# V3.net
KiCad netlist of a schematic drawn in Altium Designer
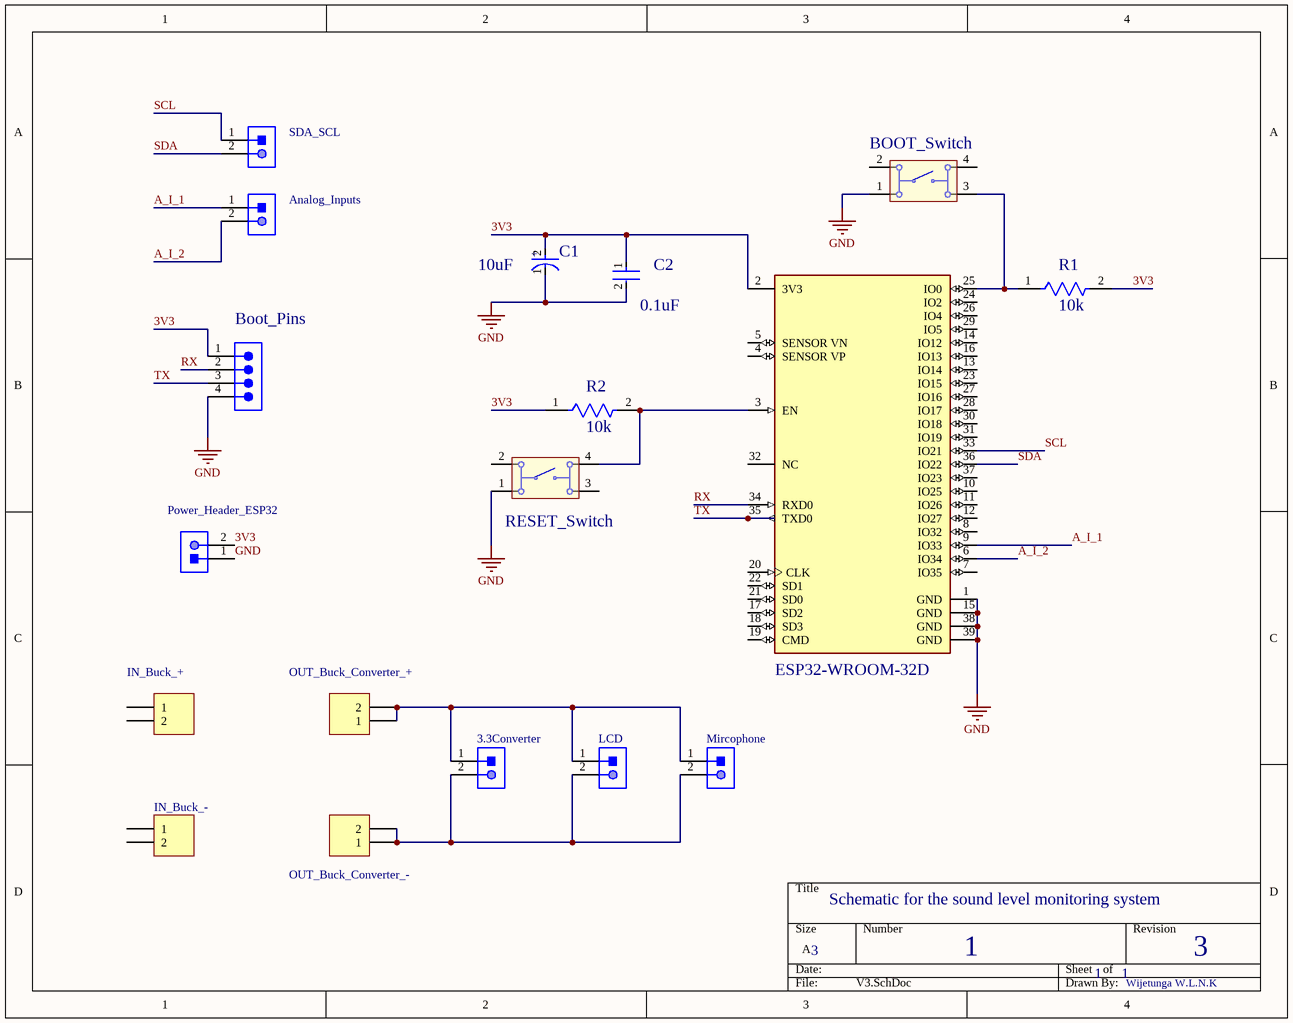
[diagram p0: V3.SchDoc]

(export (version "E")
  (design (tool "Eeschema 10.0.6"))
  (components
    (comp (ref "3.3Converter")
      (value "B2P-VH(LF)(SN)")
      (footprint "JST-B2P-VH(LF)(SN)_V")
      (fields (field (name "MANUFACTURER") "JST"))
      (libsource (lib "University of Moratuwa") (part "CN-1P-M-R2"))
    )
    (comp (ref "Analog_Inputs")
      (value "B2P-VH(LF)(SN)")
      (footprint "JST-B2P-VH(LF)(SN)_V")
      (fields (field (name "MANUFACTURER") "JST"))
      (libsource (lib "University of Moratuwa") (part "CN-1P-M-R2"))
    )
    (comp (ref "Boot_Pins")
      (value "TSW-104-08-L-S")
      (footprint "SMTC-TSW-104-08-X-S")
      (description "0.025\" SQ Post Header, Through-hole, Vertical, -55 to 125 degC, 2.54 mm Pitch, 4-Pin, Male, RoHS")
      (fields (field (name "MANUFACTURER") "Samtec"))
      (libsource (lib "Altium Content Vault") (part "SMTC-TSW-104-08-X-S"))
    )
    (comp (ref "BOOT_Switch")
      (value "430471025826")
      (footprint "430471025826")
      (description "WS-TASV SMD Tact Switch 6X6 mm")
      (fields (field (name "MANUFACTURER") "Wuerth Elektronik"))
      (libsource (lib "Altium Content Vault") (part "WE-TACT-SW-4_A"))
    )
    (comp (ref "C1")
      (value "10uF")
      (footprint "FP-RAD-TH-D_10_0_5-L_16_1-MFG")
      (description "Aluminum Electrolytic Capacitors (Radial Lead Type) AEC-Q200 Qualified 1000uF ±20% 10V")
      (fields (field (name "VOLTAGE") "10V") (field (name "TOLERANCE") "20%"))
      (libsource (lib "Altium Content Vault") (part "a00bbbee19879c290e62620ae7e47b1"))
    )
    (comp (ref "C2")
      (value "0.1uF")
      (footprint "FP-RCE0DB-MFG")
      (description "Cap Ceramic 100nF 50V X7R ±10% Radial 2.5mm +125°C Ammo Pack")
      (fields (field (name "TOLERANCE") "10%"))
      (libsource (lib "Altium Content Vault") (part "b4654b650e69147ec39a6b967a45e02"))
    )
    (comp (ref "ESP32-WROOM-32D")
      (value "ESP32-WROOM-32D")
      (footprint "FP-ESP32-WROOM-32D-MFG")
      (description "WIFI MODULE 32MBITS SPI FLASH")
      (fields
        (field (name "OCTOPART") "https://octopart.com/esp32-wroom-32d-espressif+systems-91040050")
        (field (name "MANUFACTURER") "Espressif Systems")
      )
      (libsource (lib "Altium Content Vault") (part "a031a76f8c27026a7a7f4657ff233a3"))
    )
    (comp (ref "IN_Buck_+")
      (value "Header 2")
      (footprint "HDR1X2")
      (description "Header, 2-Pin")
      (fields (field (name "PUBLISHER") "Altium Limited"))
      (libsource (lib "") (part "Header 2H_1"))
    )
    (comp (ref "IN_Buck_-")
      (value "Header 2")
      (footprint "HDR1X2")
      (description "Header, 2-Pin")
      (fields (field (name "PUBLISHER") "Altium Limited"))
      (libsource (lib "") (part "Header 2H_1"))
    )
    (comp (ref "LCD")
      (value "B2P-VH(LF)(SN)")
      (footprint "JST-B2P-VH(LF)(SN)_V")
      (fields (field (name "MANUFACTURER") "JST"))
      (libsource (lib "University of Moratuwa") (part "CN-1P-M-R2"))
    )
    (comp (ref "Mircophone")
      (value "B2P-VH(LF)(SN)")
      (footprint "JST-B2P-VH(LF)(SN)_V")
      (fields (field (name "MANUFACTURER") "JST"))
      (libsource (lib "University of Moratuwa") (part "CN-1P-M-R2"))
    )
    (comp (ref "OUT_Buck_Converter_+")
      (value "Header 2")
      (footprint "HDR1X2")
      (description "Header, 2-Pin")
      (fields (field (name "PUBLISHER") "Altium Limited"))
      (libsource (lib "University of Moratuwa") (part "Header 2H"))
    )
    (comp (ref "OUT_Buck_Converter_-")
      (value "Header 2")
      (footprint "HDR1X2")
      (description "Header, 2-Pin")
      (fields (field (name "PUBLISHER") "Altium Limited"))
      (libsource (lib "University of Moratuwa") (part "Header 2H"))
    )
    (comp (ref "Power_Header_ESP32")
      (value "B2P-VH(LF)(SN)")
      (footprint "JST-B2P-VH(LF)(SN)_V")
      (fields (field (name "MANUFACTURER") "JST"))
      (libsource (lib "") (part "CN-1P-M-R2_1"))
    )
    (comp (ref "R1")
      (value "10k")
      (footprint "FP-MBB0207-MFG")
      (description "RES 10K OHM 0.6W 1% AXIAL")
      (fields (field (name "TOLERANCE") "1%"))
      (libsource (lib "Altium Content Vault") (part "1029c3af85768c4190bb7ad29bc67b5"))
    )
    (comp (ref "R2")
      (value "10k")
      (footprint "FP-MBB0207-MFG")
      (description "RES 10K OHM 0.6W 1% AXIAL")
      (fields (field (name "TOLERANCE") "1%"))
      (libsource (lib "Altium Content Vault") (part "1029c3af85768c4190bb7ad29bc67b5"))
    )
    (comp (ref "RESET_Switch")
      (value "430471025826")
      (footprint "430471025826")
      (description "WS-TASV SMD Tact Switch 6X6 mm")
      (fields (field (name "MANUFACTURER") "Wuerth Elektronik"))
      (libsource (lib "Altium Content Vault") (part "WE-TACT-SW-4_A"))
    )
    (comp (ref "SDA_SCL")
      (value "B2P-VH(LF)(SN)")
      (footprint "JST-B2P-VH(LF)(SN)_V")
      (fields (field (name "MANUFACTURER") "JST"))
      (libsource (lib "University of Moratuwa") (part "CN-1P-M-R2"))
    )
  )
  (nets
    (net (code "1") (name "/3V3") (class "Default")
      (node (ref "Boot_Pins") (pin "1") (pinfunction "1_1") (pintype "passive"))
      (node (ref "C1") (pin "2") (pinfunction "A_2") (pintype "passive"))
      (node (ref "C2") (pin "1") (pinfunction "1_1") (pintype "passive"))
      (node (ref "ESP32-WROOM-32D") (pin "2") (pinfunction "3V3_2") (pintype "power_in"))
      (node (ref "Power_Header_ESP32") (pin "2") (pinfunction "2_2") (pintype "passive"))
      (node (ref "R1") (pin "2") (pinfunction "2_2") (pintype "passive"))
      (node (ref "R2") (pin "1") (pinfunction "1_1") (pintype "passive"))
    )
    (net (code "2") (name "/A_I_1") (class "Default")
      (node (ref "Analog_Inputs") (pin "1") (pinfunction "1_1") (pintype "passive"))
      (node (ref "ESP32-WROOM-32D") (pin "9") (pinfunction "IO33_9") (pintype "bidirectional"))
    )
    (net (code "3") (name "/A_I_2") (class "Default")
      (node (ref "Analog_Inputs") (pin "2") (pinfunction "2_2") (pintype "passive"))
      (node (ref "ESP32-WROOM-32D") (pin "6") (pinfunction "IO34_6") (pintype "bidirectional"))
    )
    (net (code "4") (name "/RX") (class "Default")
      (node (ref "Boot_Pins") (pin "2") (pinfunction "2_2") (pintype "passive"))
      (node (ref "ESP32-WROOM-32D") (pin "34") (pinfunction "RXD0_34") (pintype "input"))
    )
    (net (code "5") (name "/SCL") (class "Default")
      (node (ref "ESP32-WROOM-32D") (pin "33") (pinfunction "IO21_33") (pintype "bidirectional"))
      (node (ref "SDA_SCL") (pin "1") (pinfunction "1_1") (pintype "passive"))
    )
    (net (code "6") (name "/SDA") (class "Default")
      (node (ref "ESP32-WROOM-32D") (pin "36") (pinfunction "IO22_36") (pintype "bidirectional"))
      (node (ref "SDA_SCL") (pin "2") (pinfunction "2_2") (pintype "passive"))
    )
    (net (code "7") (name "/TX") (class "Default")
      (node (ref "Boot_Pins") (pin "3") (pinfunction "3_3") (pintype "passive"))
      (node (ref "ESP32-WROOM-32D") (pin "35") (pinfunction "TXD0_35") (pintype "output"))
    )
    (net (code "8") (name "GND") (class "Default")
      (node (ref "BOOT_Switch") (pin "1") (pinfunction "1_1") (pintype "passive"))
      (node (ref "Boot_Pins") (pin "4") (pinfunction "4_4") (pintype "passive"))
      (node (ref "C1") (pin "1") (pinfunction "C_1") (pintype "passive"))
      (node (ref "C2") (pin "2") (pinfunction "2_2") (pintype "passive"))
      (node (ref "ESP32-WROOM-32D") (pin "1") (pinfunction "GND_1") (pintype "power_in"))
      (node (ref "ESP32-WROOM-32D") (pin "15") (pinfunction "GND_15") (pintype "power_in"))
      (node (ref "ESP32-WROOM-32D") (pin "38") (pinfunction "GND_38") (pintype "power_in"))
      (node (ref "ESP32-WROOM-32D") (pin "39") (pinfunction "GND_39") (pintype "power_in"))
      (node (ref "Power_Header_ESP32") (pin "1") (pinfunction "1_1") (pintype "passive"))
      (node (ref "RESET_Switch") (pin "1") (pinfunction "1_1") (pintype "passive"))
    )
    (net (code "9") (name "Net-(3.3Converter-Pad1)") (class "Default")
      (node (ref "3.3Converter") (pin "1") (pinfunction "1_1") (pintype "passive"))
      (node (ref "LCD") (pin "1") (pinfunction "1_1") (pintype "passive"))
      (node (ref "Mircophone") (pin "1") (pinfunction "1_1") (pintype "passive"))
      (node (ref "OUT_Buck_Converter_+") (pin "1") (pinfunction "1_1") (pintype "passive"))
      (node (ref "OUT_Buck_Converter_+") (pin "2") (pinfunction "2_2") (pintype "passive"))
    )
    (net (code "10") (name "Net-(3.3Converter-Pad2)") (class "Default")
      (node (ref "3.3Converter") (pin "2") (pinfunction "2_2") (pintype "passive"))
      (node (ref "LCD") (pin "2") (pinfunction "2_2") (pintype "passive"))
      (node (ref "Mircophone") (pin "2") (pinfunction "2_2") (pintype "passive"))
      (node (ref "OUT_Buck_Converter_-") (pin "1") (pinfunction "1_1") (pintype "passive"))
      (node (ref "OUT_Buck_Converter_-") (pin "2") (pinfunction "2_2") (pintype "passive"))
    )
    (net (code "11") (name "Net-(ESP32-WROOM-32D-EN)") (class "Default")
      (node (ref "ESP32-WROOM-32D") (pin "3") (pinfunction "EN_3") (pintype "input"))
      (node (ref "R2") (pin "2") (pinfunction "2_2") (pintype "passive"))
      (node (ref "RESET_Switch") (pin "4") (pinfunction "4_4") (pintype "passive"))
    )
    (net (code "12") (name "Net-(ESP32-WROOM-32D-IO0)") (class "Default")
      (node (ref "BOOT_Switch") (pin "3") (pinfunction "3_3") (pintype "passive"))
      (node (ref "ESP32-WROOM-32D") (pin "25") (pinfunction "IO0_25") (pintype "bidirectional"))
      (node (ref "R1") (pin "1") (pinfunction "1_1") (pintype "passive"))
    )
    (net (code "13") (name "unconnected-(BOOT_Switch-Pad2)") (class "Default")
      (node (ref "BOOT_Switch") (pin "2") (pinfunction "2_2") (pintype "passive"))
    )
    (net (code "14") (name "unconnected-(BOOT_Switch-Pad4)") (class "Default")
      (node (ref "BOOT_Switch") (pin "4") (pinfunction "4_4") (pintype "passive"))
    )
    (net (code "15") (name "unconnected-(ESP32-WROOM-32D-CLK-Pad20)") (class "Default")
      (node (ref "ESP32-WROOM-32D") (pin "20") (pinfunction "CLK_20") (pintype "input"))
    )
    (net (code "16") (name "unconnected-(ESP32-WROOM-32D-CMD-Pad19)") (class "Default")
      (node (ref "ESP32-WROOM-32D") (pin "19") (pinfunction "CMD_19") (pintype "bidirectional"))
    )
    (net (code "17") (name "unconnected-(ESP32-WROOM-32D-IO2-Pad24)") (class "Default")
      (node (ref "ESP32-WROOM-32D") (pin "24") (pinfunction "IO2_24") (pintype "bidirectional"))
    )
    (net (code "18") (name "unconnected-(ESP32-WROOM-32D-IO4-Pad26)") (class "Default")
      (node (ref "ESP32-WROOM-32D") (pin "26") (pinfunction "IO4_26") (pintype "bidirectional"))
    )
    (net (code "19") (name "unconnected-(ESP32-WROOM-32D-IO5-Pad29)") (class "Default")
      (node (ref "ESP32-WROOM-32D") (pin "29") (pinfunction "IO5_29") (pintype "bidirectional"))
    )
    (net (code "20") (name "unconnected-(ESP32-WROOM-32D-IO12-Pad14)") (class "Default")
      (node (ref "ESP32-WROOM-32D") (pin "14") (pinfunction "IO12_14") (pintype "bidirectional"))
    )
    (net (code "21") (name "unconnected-(ESP32-WROOM-32D-IO13-Pad16)") (class "Default")
      (node (ref "ESP32-WROOM-32D") (pin "16") (pinfunction "IO13_16") (pintype "bidirectional"))
    )
    (net (code "22") (name "unconnected-(ESP32-WROOM-32D-IO14-Pad13)") (class "Default")
      (node (ref "ESP32-WROOM-32D") (pin "13") (pinfunction "IO14_13") (pintype "bidirectional"))
    )
    (net (code "23") (name "unconnected-(ESP32-WROOM-32D-IO15-Pad23)") (class "Default")
      (node (ref "ESP32-WROOM-32D") (pin "23") (pinfunction "IO15_23") (pintype "bidirectional"))
    )
    (net (code "24") (name "unconnected-(ESP32-WROOM-32D-IO16-Pad27)") (class "Default")
      (node (ref "ESP32-WROOM-32D") (pin "27") (pinfunction "IO16_27") (pintype "bidirectional"))
    )
    (net (code "25") (name "unconnected-(ESP32-WROOM-32D-IO17-Pad28)") (class "Default")
      (node (ref "ESP32-WROOM-32D") (pin "28") (pinfunction "IO17_28") (pintype "bidirectional"))
    )
    (net (code "26") (name "unconnected-(ESP32-WROOM-32D-IO18-Pad30)") (class "Default")
      (node (ref "ESP32-WROOM-32D") (pin "30") (pinfunction "IO18_30") (pintype "bidirectional"))
    )
    (net (code "27") (name "unconnected-(ESP32-WROOM-32D-IO19-Pad31)") (class "Default")
      (node (ref "ESP32-WROOM-32D") (pin "31") (pinfunction "IO19_31") (pintype "bidirectional"))
    )
    (net (code "28") (name "unconnected-(ESP32-WROOM-32D-IO23-Pad37)") (class "Default")
      (node (ref "ESP32-WROOM-32D") (pin "37") (pinfunction "IO23_37") (pintype "bidirectional"))
    )
    (net (code "29") (name "unconnected-(ESP32-WROOM-32D-IO25-Pad10)") (class "Default")
      (node (ref "ESP32-WROOM-32D") (pin "10") (pinfunction "IO25_10") (pintype "bidirectional"))
    )
    (net (code "30") (name "unconnected-(ESP32-WROOM-32D-IO26-Pad11)") (class "Default")
      (node (ref "ESP32-WROOM-32D") (pin "11") (pinfunction "IO26_11") (pintype "bidirectional"))
    )
    (net (code "31") (name "unconnected-(ESP32-WROOM-32D-IO27-Pad12)") (class "Default")
      (node (ref "ESP32-WROOM-32D") (pin "12") (pinfunction "IO27_12") (pintype "bidirectional"))
    )
    (net (code "32") (name "unconnected-(ESP32-WROOM-32D-IO32-Pad8)") (class "Default")
      (node (ref "ESP32-WROOM-32D") (pin "8") (pinfunction "IO32_8") (pintype "bidirectional"))
    )
    (net (code "33") (name "unconnected-(ESP32-WROOM-32D-IO35-Pad7)") (class "Default")
      (node (ref "ESP32-WROOM-32D") (pin "7") (pinfunction "IO35_7") (pintype "bidirectional"))
    )
    (net (code "34") (name "unconnected-(ESP32-WROOM-32D-NC-Pad32)") (class "Default")
      (node (ref "ESP32-WROOM-32D") (pin "32") (pinfunction "NC_32") (pintype "passive"))
    )
    (net (code "35") (name "unconnected-(ESP32-WROOM-32D-SD0-Pad21)") (class "Default")
      (node (ref "ESP32-WROOM-32D") (pin "21") (pinfunction "SD0_21") (pintype "bidirectional"))
    )
    (net (code "36") (name "unconnected-(ESP32-WROOM-32D-SD1-Pad22)") (class "Default")
      (node (ref "ESP32-WROOM-32D") (pin "22") (pinfunction "SD1_22") (pintype "bidirectional"))
    )
    (net (code "37") (name "unconnected-(ESP32-WROOM-32D-SD2-Pad17)") (class "Default")
      (node (ref "ESP32-WROOM-32D") (pin "17") (pinfunction "SD2_17") (pintype "bidirectional"))
    )
    (net (code "38") (name "unconnected-(ESP32-WROOM-32D-SD3-Pad18)") (class "Default")
      (node (ref "ESP32-WROOM-32D") (pin "18") (pinfunction "SD3_18") (pintype "bidirectional"))
    )
    (net (code "39") (name "unconnected-(ESP32-WROOM-32D-SENSOR_VN-Pad5)") (class "Default")
      (node (ref "ESP32-WROOM-32D") (pin "5") (pinfunction "SENSOR_VN_5") (pintype "bidirectional"))
    )
    (net (code "40") (name "unconnected-(ESP32-WROOM-32D-SENSOR_VP-Pad4)") (class "Default")
      (node (ref "ESP32-WROOM-32D") (pin "4") (pinfunction "SENSOR_VP_4") (pintype "bidirectional"))
    )
    (net (code "41") (name "unconnected-(IN_Buck_+-Pad1)") (class "Default")
      (node (ref "IN_Buck_+") (pin "1") (pinfunction "1_1") (pintype "passive"))
    )
    (net (code "42") (name "unconnected-(IN_Buck_+-Pad2)") (class "Default")
      (node (ref "IN_Buck_+") (pin "2") (pinfunction "2_2") (pintype "passive"))
    )
    (net (code "43") (name "unconnected-(IN_Buck_--Pad1)") (class "Default")
      (node (ref "IN_Buck_-") (pin "1") (pinfunction "1_1") (pintype "passive"))
    )
    (net (code "44") (name "unconnected-(IN_Buck_--Pad2)") (class "Default")
      (node (ref "IN_Buck_-") (pin "2") (pinfunction "2_2") (pintype "passive"))
    )
    (net (code "45") (name "unconnected-(RESET_Switch-Pad2)") (class "Default")
      (node (ref "RESET_Switch") (pin "2") (pinfunction "2_2") (pintype "passive"))
    )
    (net (code "46") (name "unconnected-(RESET_Switch-Pad3)") (class "Default")
      (node (ref "RESET_Switch") (pin "3") (pinfunction "3_3") (pintype "passive"))
    )
  )
)
